# Microphone.net
KiCad netlist of a schematic drawn in Altium Designer
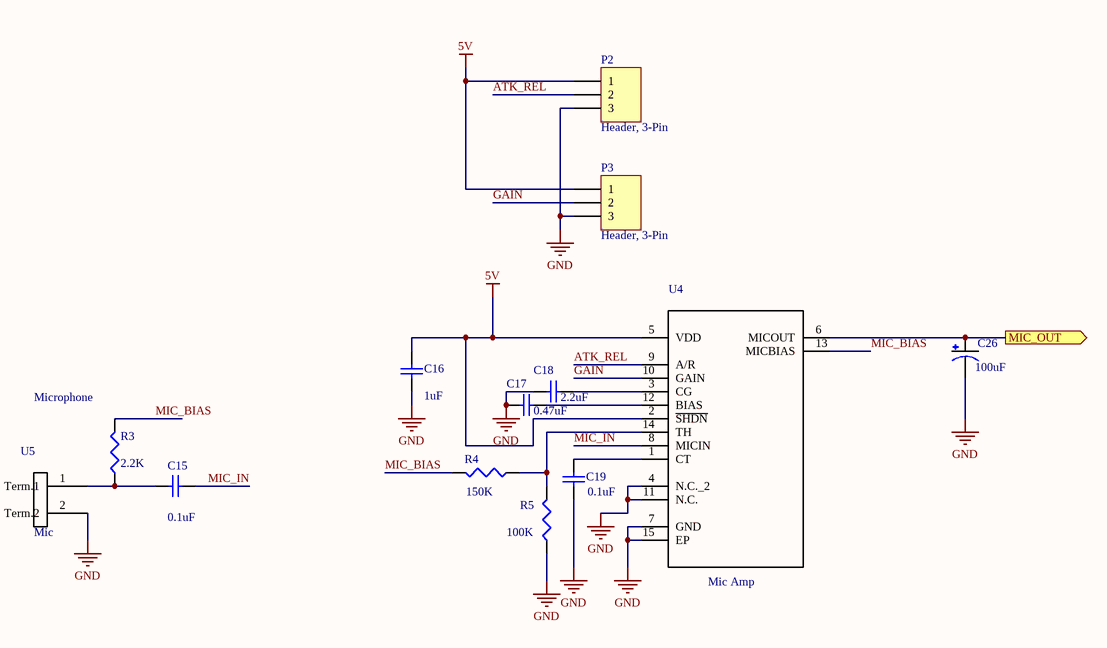
[diagram p0: Microphone.SchDoc]

(export (version "E")
  (design (tool "Eeschema 10.0.6"))
  (components
    (comp (ref "C15")
      (value "0.1uF")
      (footprint "1608[0603]")
      (description "Capacitor (Semiconductor SIM Model)")
      (fields (field (name "PUBLISHER") "Altium Limited"))
      (libsource (lib "Miscellaneous Devices") (part "Cap Semi"))
    )
    (comp (ref "C16")
      (value "1uF")
      (footprint "1608[0603]")
      (description "Capacitor (Semiconductor SIM Model)")
      (fields (field (name "PUBLISHER") "Altium Limited"))
      (libsource (lib "Miscellaneous Devices") (part "Cap Semi"))
    )
    (comp (ref "C17")
      (value "0.47uF")
      (footprint "1608[0603]")
      (description "Capacitor (Semiconductor SIM Model)")
      (fields (field (name "PUBLISHER") "Altium Limited"))
      (libsource (lib "Miscellaneous Devices") (part "Cap Semi"))
    )
    (comp (ref "C18")
      (value "2.2uF")
      (footprint "1608[0603]")
      (description "Capacitor (Semiconductor SIM Model)")
      (fields (field (name "PUBLISHER") "Altium Limited"))
      (libsource (lib "Miscellaneous Devices") (part "Cap Semi"))
    )
    (comp (ref "C19")
      (value "0.1uF")
      (footprint "1608[0603]")
      (description "Capacitor (Semiconductor SIM Model)")
      (fields (field (name "PUBLISHER") "Altium Limited"))
      (libsource (lib "Miscellaneous Devices") (part "Cap Semi"))
    )
    (comp (ref "C26")
      (value "100uF")
      (footprint "CAPAE1050X1050N")
      (description "146 CTI Series 50 V 100 uF 10 x 10 x 10 mm SMT CAN Electrolytic Capacitor")
      (fields (field (name "MF") "Vishay") (field (name "MP") "MAL214699103E3"))
      (libsource (lib "LowPower_3ER_Parts") (part "MAL214699103E3"))
    )
    (comp (ref "P2")
      (value "Header, 3-Pin")
      (footprint "HDR1X3")
      (fields (field (name "PUBLISHER") "Altium Limited"))
      (libsource (lib "Miscellaneous Connectors") (part "Header 3"))
    )
    (comp (ref "P3")
      (value "Header, 3-Pin")
      (footprint "HDR1X3")
      (fields (field (name "PUBLISHER") "Altium Limited"))
      (libsource (lib "Miscellaneous Connectors") (part "Header 3"))
    )
    (comp (ref "R3")
      (value "2.2K")
      (footprint "J1-0603")
      (description "Resistor")
      (fields (field (name "PUBLISHER") "Altium Limited"))
      (libsource (lib "Miscellaneous Devices") (part "Res3"))
    )
    (comp (ref "R4")
      (value "150K")
      (footprint "J1-0603")
      (description "Resistor")
      (fields (field (name "PUBLISHER") "Altium Limited"))
      (libsource (lib "Miscellaneous Devices") (part "Res3"))
    )
    (comp (ref "R5")
      (value "100K")
      (footprint "J1-0603")
      (description "Resistor")
      (fields (field (name "PUBLISHER") "Altium Limited"))
      (libsource (lib "Miscellaneous Devices") (part "Res3"))
    )
    (comp (ref "U4")
      (value "Mic Amp")
      (footprint "DFN300X300X80-15N")
      (description "Audio Amp Microphone 1-CH Mono Class-AB 14-Pin TDFN EP T/R")
      (fields (field (name "MF") "Maxim Integrated") (field (name "MP") "MAX9814ETD+T"))
      (libsource (lib "LowPower_3ER_Parts") (part "MAX9814ETD+T"))
    )
    (comp (ref "U5")
      (value "Mic")
      (footprint "CMA-4544PF-W")
      (libsource (lib "microphone") (part "Component_1"))
    )
  )
  (nets
    (net (code "1") (name "/ATK_REL") (class "Default")
      (node (ref "P2") (pin "2") (pinfunction "2_2") (pintype "passive"))
      (node (ref "U4") (pin "9") (pinfunction "A/R_9") (pintype "passive"))
    )
    (net (code "2") (name "/GAIN") (class "Default")
      (node (ref "P3") (pin "2") (pinfunction "2_2") (pintype "passive"))
      (node (ref "U4") (pin "10") (pinfunction "GAIN_10") (pintype "passive"))
    )
    (net (code "3") (name "/MIC_BIAS") (class "Default")
      (node (ref "R3") (pin "2") (pinfunction "2_2") (pintype "passive"))
      (node (ref "R4") (pin "2") (pinfunction "2_2") (pintype "passive"))
      (node (ref "U4") (pin "13") (pinfunction "MICBIAS_13") (pintype "passive"))
    )
    (net (code "4") (name "/MIC_IN") (class "Default")
      (node (ref "C15") (pin "2") (pinfunction "2_2") (pintype "passive"))
      (node (ref "U4") (pin "8") (pinfunction "MICIN_8") (pintype "passive"))
    )
    (net (code "5") (name "/MIC_OUT") (class "Default")
      (node (ref "C26") (pin "1") (pinfunction "POS_1") (pintype "passive"))
      (node (ref "U4") (pin "6") (pinfunction "MICOUT_6") (pintype "passive"))
    )
    (net (code "6") (name "5V") (class "Default")
      (node (ref "C16") (pin "2") (pinfunction "2_2") (pintype "passive"))
      (node (ref "P2") (pin "1") (pinfunction "1_1") (pintype "passive"))
      (node (ref "P3") (pin "1") (pinfunction "1_1") (pintype "passive"))
      (node (ref "U4") (pin "2") (pinfunction "~{SHDN}_2") (pintype "passive"))
      (node (ref "U4") (pin "5") (pinfunction "VDD_5") (pintype "power_in"))
    )
    (net (code "7") (name "GND") (class "Default")
      (node (ref "C16") (pin "1") (pinfunction "1_1") (pintype "passive"))
      (node (ref "C17") (pin "2") (pinfunction "2_2") (pintype "passive"))
      (node (ref "C18") (pin "2") (pinfunction "2_2") (pintype "passive"))
      (node (ref "C19") (pin "1") (pinfunction "1_1") (pintype "passive"))
      (node (ref "C26") (pin "2") (pinfunction "NEG_2") (pintype "passive"))
      (node (ref "P2") (pin "3") (pinfunction "3_3") (pintype "passive"))
      (node (ref "P3") (pin "3") (pinfunction "3_3") (pintype "passive"))
      (node (ref "R5") (pin "1") (pinfunction "1_1") (pintype "passive"))
      (node (ref "U4") (pin "11") (pinfunction "N.C._11") (pintype "passive"))
      (node (ref "U4") (pin "15") (pinfunction "EP_15") (pintype "passive"))
      (node (ref "U4") (pin "4") (pinfunction "N.C._2_4") (pintype "passive"))
      (node (ref "U4") (pin "7") (pinfunction "GND_7") (pintype "passive"))
      (node (ref "U5") (pin "2") (pinfunction "Term.2_2") (pintype "passive"))
    )
    (net (code "8") (name "Net-(U4-BIAS)") (class "Default")
      (node (ref "C17") (pin "1") (pinfunction "1_1") (pintype "passive"))
      (node (ref "U4") (pin "12") (pinfunction "BIAS_12") (pintype "passive"))
    )
    (net (code "9") (name "Net-(U4-CG)") (class "Default")
      (node (ref "C18") (pin "1") (pinfunction "1_1") (pintype "passive"))
      (node (ref "U4") (pin "3") (pinfunction "CG_3") (pintype "passive"))
    )
    (net (code "10") (name "Net-(U4-CT)") (class "Default")
      (node (ref "C19") (pin "2") (pinfunction "2_2") (pintype "passive"))
      (node (ref "U4") (pin "1") (pinfunction "CT_1") (pintype "passive"))
    )
    (net (code "11") (name "Net-(U4-TH)") (class "Default")
      (node (ref "R4") (pin "1") (pinfunction "1_1") (pintype "passive"))
      (node (ref "R5") (pin "2") (pinfunction "2_2") (pintype "passive"))
      (node (ref "U4") (pin "14") (pinfunction "TH_14") (pintype "passive"))
    )
    (net (code "12") (name "Net-(U5-Term.1)") (class "Default")
      (node (ref "C15") (pin "1") (pinfunction "1_1") (pintype "passive"))
      (node (ref "R3") (pin "1") (pinfunction "1_1") (pintype "passive"))
      (node (ref "U5") (pin "1") (pinfunction "Term.1_1") (pintype "passive"))
    )
  )
)
